# LTC6811_slave_12s_rev0.net
KiCad netlist of a schematic drawn in EAGLE
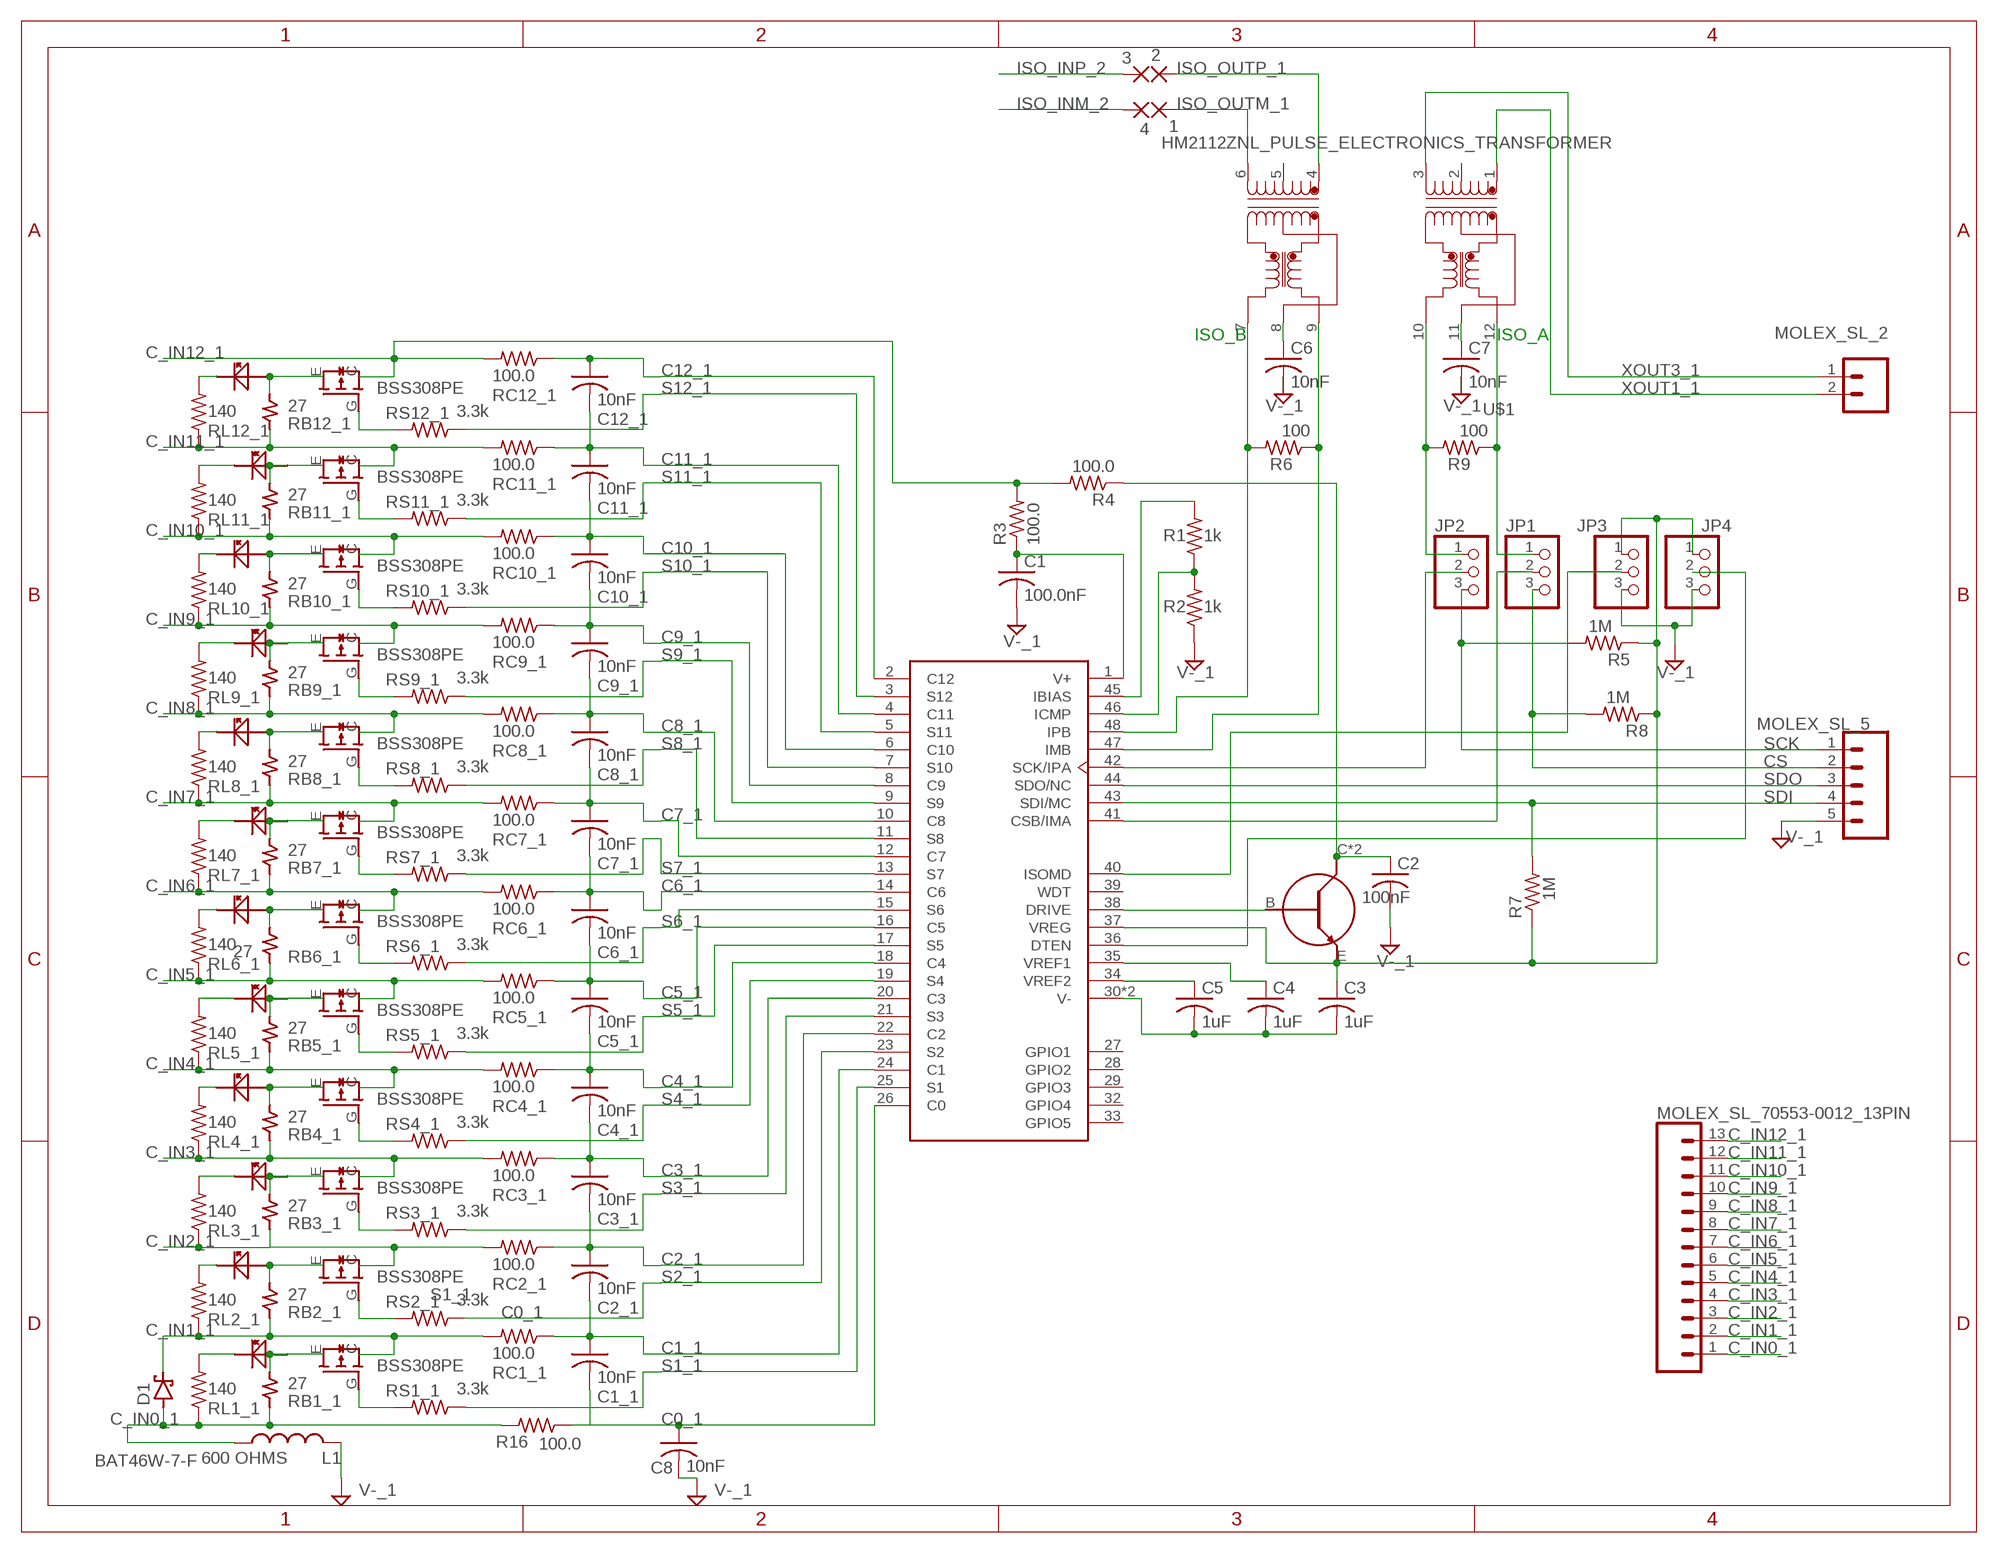
[diagram p0: schematic, sheet 1]

(export (version "E")
  (design (tool "Eeschema 10.0.6"))
  (components
    (comp (ref "1")
      (value "WIREPAD2,15/1,0")
      (footprint "eagle-import:2,15_1,0")
      (libsource (lib "eagle-import") (part "WIREPAD2,15/1,0"))
    )
    (comp (ref "2")
      (value "WIREPAD2,15/1,0")
      (footprint "eagle-import:2,15_1,0")
      (libsource (lib "eagle-import") (part "WIREPAD2,15/1,0"))
    )
    (comp (ref "3")
      (value "WIREPAD2,15/1,0")
      (footprint "eagle-import:2,15_1,0")
      (libsource (lib "eagle-import") (part "WIREPAD2,15/1,0"))
    )
    (comp (ref "4")
      (value "WIREPAD2,15/1,0")
      (footprint "eagle-import:2,15_1,0")
      (libsource (lib "eagle-import") (part "WIREPAD2,15/1,0"))
    )
    (comp (ref "C1")
      (value "100.0nF")
      (footprint "eagle-import:C0805")
      (libsource (lib "eagle-import") (part "C-USC0805"))
    )
    (comp (ref "C1_1")
      (value "10nF")
      (footprint "eagle-import:C0805")
      (libsource (lib "eagle-import") (part "C-USC0805"))
    )
    (comp (ref "C2")
      (value "100nF")
      (footprint "eagle-import:C0805")
      (libsource (lib "eagle-import") (part "C-USC0805"))
    )
    (comp (ref "C2_1")
      (value "10nF")
      (footprint "eagle-import:C0805")
      (libsource (lib "eagle-import") (part "C-USC0805"))
    )
    (comp (ref "C3")
      (value "1uF")
      (footprint "eagle-import:C0805")
      (libsource (lib "eagle-import") (part "C-USC0805"))
    )
    (comp (ref "C3_1")
      (value "10nF")
      (footprint "eagle-import:C0805")
      (libsource (lib "eagle-import") (part "C-USC0805"))
    )
    (comp (ref "C4")
      (value "1uF")
      (footprint "eagle-import:C0805")
      (libsource (lib "eagle-import") (part "C-USC0805"))
    )
    (comp (ref "C4_1")
      (value "10nF")
      (footprint "eagle-import:C0805")
      (libsource (lib "eagle-import") (part "C-USC0805"))
    )
    (comp (ref "C5")
      (value "1uF")
      (footprint "eagle-import:C0805")
      (libsource (lib "eagle-import") (part "C-USC0805"))
    )
    (comp (ref "C5_1")
      (value "10nF")
      (footprint "eagle-import:C0805")
      (libsource (lib "eagle-import") (part "C-USC0805"))
    )
    (comp (ref "C6")
      (value "10nF")
      (footprint "eagle-import:C0805")
      (libsource (lib "eagle-import") (part "C-USC0805"))
    )
    (comp (ref "C6_1")
      (value "10nF")
      (footprint "eagle-import:C0805")
      (libsource (lib "eagle-import") (part "C-USC0805"))
    )
    (comp (ref "C7")
      (value "10nF")
      (footprint "eagle-import:C0805")
      (libsource (lib "eagle-import") (part "C-USC0805"))
    )
    (comp (ref "C7_1")
      (value "10nF")
      (footprint "eagle-import:C0805")
      (libsource (lib "eagle-import") (part "C-USC0805"))
    )
    (comp (ref "C8")
      (value "10nF")
      (footprint "eagle-import:C0805")
      (libsource (lib "eagle-import") (part "C-USC0805"))
    )
    (comp (ref "C8_1")
      (value "10nF")
      (footprint "eagle-import:C0805")
      (libsource (lib "eagle-import") (part "C-USC0805"))
    )
    (comp (ref "C9_1")
      (value "10nF")
      (footprint "eagle-import:C0805")
      (libsource (lib "eagle-import") (part "C-USC0805"))
    )
    (comp (ref "C10_1")
      (value "10nF")
      (footprint "eagle-import:C0805")
      (libsource (lib "eagle-import") (part "C-USC0805"))
    )
    (comp (ref "C11_1")
      (value "10nF")
      (footprint "eagle-import:C0805")
      (libsource (lib "eagle-import") (part "C-USC0805"))
    )
    (comp (ref "C12_1")
      (value "10nF")
      (footprint "eagle-import:C0805")
      (libsource (lib "eagle-import") (part "C-USC0805"))
    )
    (comp (ref "D1")
      (value "BAT46W-7-F")
      (footprint "eagle-import:SOD123")
      (libsource (lib "eagle-import") (part "BAT46W-7-F"))
    )
    (comp (ref "DZT5551-13")
      (value "DZT5551-13")
      (footprint "eagle-import:SOT223-4")
      (libsource (lib "eagle-import") (part "DZT5551-13"))
    )
    (comp (ref "JP1")
      (value "PINHD-1X3")
      (footprint "eagle-import:1X03")
      (libsource (lib "eagle-import") (part "PINHD-1X3"))
    )
    (comp (ref "JP2")
      (value "PINHD-1X3")
      (footprint "eagle-import:1X03")
      (libsource (lib "eagle-import") (part "PINHD-1X3"))
    )
    (comp (ref "JP3")
      (value "PINHD-1X3")
      (footprint "eagle-import:1X03")
      (libsource (lib "eagle-import") (part "PINHD-1X3"))
    )
    (comp (ref "JP4")
      (value "PINHD-1X3")
      (footprint "eagle-import:1X03")
      (libsource (lib "eagle-import") (part "PINHD-1X3"))
    )
    (comp (ref "L1")
      (value "600 OHMS")
      (footprint "eagle-import:0805_COMPONENT")
      (libsource (lib "eagle-import") (part "0805_FERRITEBEAD_INDUCTOR"))
    )
    (comp (ref "LED1_3")
      (value "LED_0805")
      (footprint "eagle-import:0805_COMPONENT")
      (libsource (lib "eagle-import") (part "LED_0805"))
    )
    (comp (ref "LED1_4")
      (value "LED_0805")
      (footprint "eagle-import:0805_COMPONENT")
      (libsource (lib "eagle-import") (part "LED_0805"))
    )
    (comp (ref "LED1_5")
      (value "LED_0805")
      (footprint "eagle-import:0805_COMPONENT")
      (libsource (lib "eagle-import") (part "LED_0805"))
    )
    (comp (ref "LED1_6")
      (value "LED_0805")
      (footprint "eagle-import:0805_COMPONENT")
      (libsource (lib "eagle-import") (part "LED_0805"))
    )
    (comp (ref "LED1_7")
      (value "LED_0805")
      (footprint "eagle-import:0805_COMPONENT")
      (libsource (lib "eagle-import") (part "LED_0805"))
    )
    (comp (ref "LED1_8")
      (value "LED_0805")
      (footprint "eagle-import:0805_COMPONENT")
      (libsource (lib "eagle-import") (part "LED_0805"))
    )
    (comp (ref "LED1_9")
      (value "LED_0805")
      (footprint "eagle-import:0805_COMPONENT")
      (libsource (lib "eagle-import") (part "LED_0805"))
    )
    (comp (ref "LED1_10")
      (value "LED_0805")
      (footprint "eagle-import:0805_COMPONENT")
      (libsource (lib "eagle-import") (part "LED_0805"))
    )
    (comp (ref "LED1_11")
      (value "LED_0805")
      (footprint "eagle-import:0805_COMPONENT")
      (libsource (lib "eagle-import") (part "LED_0805"))
    )
    (comp (ref "LED1_12")
      (value "LED_0805")
      (footprint "eagle-import:0805_COMPONENT")
      (libsource (lib "eagle-import") (part "LED_0805"))
    )
    (comp (ref "LED1_13")
      (value "LED_0805")
      (footprint "eagle-import:0805_COMPONENT")
      (libsource (lib "eagle-import") (part "LED_0805"))
    )
    (comp (ref "LED1_14")
      (value "LED_0805")
      (footprint "eagle-import:0805_COMPONENT")
      (libsource (lib "eagle-import") (part "LED_0805"))
    )
    (comp (ref "MOLEX_SL_2")
      (value "CONN_02")
      (footprint "eagle-import:1X02")
      (libsource (lib "eagle-import") (part "CONN_02"))
    )
    (comp (ref "MOLEX_SL_5")
      (value "CONN_05")
      (footprint "eagle-import:1X05")
      (libsource (lib "eagle-import") (part "CONN_05"))
    )
    (comp (ref "MOLEX_SL_70553-0012_13PIN")
      (value "CONN_13")
      (footprint "eagle-import:1X13")
      (libsource (lib "eagle-import") (part "CONN_13"))
    )
    (comp (ref "R1")
      (value "1k")
      (footprint "eagle-import:R0805")
      (libsource (lib "eagle-import") (part "R-US_R0805"))
    )
    (comp (ref "R2")
      (value "1k")
      (footprint "eagle-import:R0805")
      (libsource (lib "eagle-import") (part "R-US_R0805"))
    )
    (comp (ref "R3")
      (value "100.0")
      (footprint "eagle-import:R0805")
      (libsource (lib "eagle-import") (part "R-US_R0805"))
    )
    (comp (ref "R4")
      (value "100.0")
      (footprint "eagle-import:R0805")
      (libsource (lib "eagle-import") (part "R-US_R0805"))
    )
    (comp (ref "R5")
      (value "1M")
      (footprint "eagle-import:R0805")
      (libsource (lib "eagle-import") (part "R-US_R0805"))
    )
    (comp (ref "R6")
      (value "100")
      (footprint "eagle-import:R0805")
      (libsource (lib "eagle-import") (part "R-US_R0805"))
    )
    (comp (ref "R7")
      (value "1M")
      (footprint "eagle-import:R0805")
      (libsource (lib "eagle-import") (part "R-US_R0805"))
    )
    (comp (ref "R8")
      (value "1M")
      (footprint "eagle-import:R0805")
      (libsource (lib "eagle-import") (part "R-US_R0805"))
    )
    (comp (ref "R9")
      (value "100")
      (footprint "eagle-import:R0805")
      (libsource (lib "eagle-import") (part "R-US_R0805"))
    )
    (comp (ref "R16")
      (value "100.0")
      (footprint "eagle-import:R0805")
      (libsource (lib "eagle-import") (part "R-US_R0805"))
    )
    (comp (ref "RB1_1")
      (value "27")
      (footprint "eagle-import:2817_COMPONENT")
      (libsource (lib "eagle-import") (part "2817_RESISTOR"))
    )
    (comp (ref "RB2_1")
      (value "27")
      (footprint "eagle-import:2817_COMPONENT")
      (libsource (lib "eagle-import") (part "2817_RESISTOR"))
    )
    (comp (ref "RB3_1")
      (value "27")
      (footprint "eagle-import:2817_COMPONENT")
      (libsource (lib "eagle-import") (part "2817_RESISTOR"))
    )
    (comp (ref "RB4_1")
      (value "27")
      (footprint "eagle-import:2817_COMPONENT")
      (libsource (lib "eagle-import") (part "2817_RESISTOR"))
    )
    (comp (ref "RB5_1")
      (value "27")
      (footprint "eagle-import:2817_COMPONENT")
      (libsource (lib "eagle-import") (part "2817_RESISTOR"))
    )
    (comp (ref "RB6_1")
      (value "27")
      (footprint "eagle-import:2817_COMPONENT")
      (libsource (lib "eagle-import") (part "2817_RESISTOR"))
    )
    (comp (ref "RB7_1")
      (value "27")
      (footprint "eagle-import:2817_COMPONENT")
      (libsource (lib "eagle-import") (part "2817_RESISTOR"))
    )
    (comp (ref "RB8_1")
      (value "27")
      (footprint "eagle-import:2817_COMPONENT")
      (libsource (lib "eagle-import") (part "2817_RESISTOR"))
    )
    (comp (ref "RB9_1")
      (value "27")
      (footprint "eagle-import:2817_COMPONENT")
      (libsource (lib "eagle-import") (part "2817_RESISTOR"))
    )
    (comp (ref "RB10_1")
      (value "27")
      (footprint "eagle-import:2817_COMPONENT")
      (libsource (lib "eagle-import") (part "2817_RESISTOR"))
    )
    (comp (ref "RB11_1")
      (value "27")
      (footprint "eagle-import:2817_COMPONENT")
      (libsource (lib "eagle-import") (part "2817_RESISTOR"))
    )
    (comp (ref "RB12_1")
      (value "27")
      (footprint "eagle-import:2817_COMPONENT")
      (libsource (lib "eagle-import") (part "2817_RESISTOR"))
    )
    (comp (ref "RC1_1")
      (value "100.0")
      (footprint "eagle-import:R0805")
      (libsource (lib "eagle-import") (part "R-US_R0805"))
    )
    (comp (ref "RC2_1")
      (value "100.0")
      (footprint "eagle-import:R0805")
      (libsource (lib "eagle-import") (part "R-US_R0805"))
    )
    (comp (ref "RC3_1")
      (value "100.0")
      (footprint "eagle-import:R0805")
      (libsource (lib "eagle-import") (part "R-US_R0805"))
    )
    (comp (ref "RC4_1")
      (value "100.0")
      (footprint "eagle-import:R0805")
      (libsource (lib "eagle-import") (part "R-US_R0805"))
    )
    (comp (ref "RC5_1")
      (value "100.0")
      (footprint "eagle-import:R0805")
      (libsource (lib "eagle-import") (part "R-US_R0805"))
    )
    (comp (ref "RC6_1")
      (value "100.0")
      (footprint "eagle-import:R0805")
      (libsource (lib "eagle-import") (part "R-US_R0805"))
    )
    (comp (ref "RC7_1")
      (value "100.0")
      (footprint "eagle-import:R0805")
      (libsource (lib "eagle-import") (part "R-US_R0805"))
    )
    (comp (ref "RC8_1")
      (value "100.0")
      (footprint "eagle-import:R0805")
      (libsource (lib "eagle-import") (part "R-US_R0805"))
    )
    (comp (ref "RC9_1")
      (value "100.0")
      (footprint "eagle-import:R0805")
      (libsource (lib "eagle-import") (part "R-US_R0805"))
    )
    (comp (ref "RC10_1")
      (value "100.0")
      (footprint "eagle-import:R0805")
      (libsource (lib "eagle-import") (part "R-US_R0805"))
    )
    (comp (ref "RC11_1")
      (value "100.0")
      (footprint "eagle-import:R0805")
      (libsource (lib "eagle-import") (part "R-US_R0805"))
    )
    (comp (ref "RC12_1")
      (value "100.0")
      (footprint "eagle-import:R0805")
      (libsource (lib "eagle-import") (part "R-US_R0805"))
    )
    (comp (ref "RL1_1")
      (value "140")
      (footprint "eagle-import:R0805")
      (libsource (lib "eagle-import") (part "R-US_R0805"))
    )
    (comp (ref "RL2_1")
      (value "140")
      (footprint "eagle-import:R0805")
      (libsource (lib "eagle-import") (part "R-US_R0805"))
    )
    (comp (ref "RL3_1")
      (value "140")
      (footprint "eagle-import:R0805")
      (libsource (lib "eagle-import") (part "R-US_R0805"))
    )
    (comp (ref "RL4_1")
      (value "140")
      (footprint "eagle-import:R0805")
      (libsource (lib "eagle-import") (part "R-US_R0805"))
    )
    (comp (ref "RL5_1")
      (value "140")
      (footprint "eagle-import:R0805")
      (libsource (lib "eagle-import") (part "R-US_R0805"))
    )
    (comp (ref "RL6_1")
      (value "140")
      (footprint "eagle-import:R0805")
      (libsource (lib "eagle-import") (part "R-US_R0805"))
    )
    (comp (ref "RL7_1")
      (value "140")
      (footprint "eagle-import:R0805")
      (libsource (lib "eagle-import") (part "R-US_R0805"))
    )
    (comp (ref "RL8_1")
      (value "140")
      (footprint "eagle-import:R0805")
      (libsource (lib "eagle-import") (part "R-US_R0805"))
    )
    (comp (ref "RL9_1")
      (value "140")
      (footprint "eagle-import:R0805")
      (libsource (lib "eagle-import") (part "R-US_R0805"))
    )
    (comp (ref "RL10_1")
      (value "140")
      (footprint "eagle-import:R0805")
      (libsource (lib "eagle-import") (part "R-US_R0805"))
    )
    (comp (ref "RL11_1")
      (value "140")
      (footprint "eagle-import:R0805")
      (libsource (lib "eagle-import") (part "R-US_R0805"))
    )
    (comp (ref "RL12_1")
      (value "140")
      (footprint "eagle-import:R0805")
      (libsource (lib "eagle-import") (part "R-US_R0805"))
    )
    (comp (ref "RS1_1")
      (value "3.3k")
      (footprint "eagle-import:R0805")
      (libsource (lib "eagle-import") (part "R-US_R0805"))
    )
    (comp (ref "RS2_1")
      (value "3.3k")
      (footprint "eagle-import:R0805")
      (libsource (lib "eagle-import") (part "R-US_R0805"))
    )
    (comp (ref "RS3_1")
      (value "3.3k")
      (footprint "eagle-import:R0805")
      (libsource (lib "eagle-import") (part "R-US_R0805"))
    )
    (comp (ref "RS4_1")
      (value "3.3k")
      (footprint "eagle-import:R0805")
      (libsource (lib "eagle-import") (part "R-US_R0805"))
    )
    (comp (ref "RS5_1")
      (value "3.3k")
      (footprint "eagle-import:R0805")
      (libsource (lib "eagle-import") (part "R-US_R0805"))
    )
    (comp (ref "RS6_1")
      (value "3.3k")
      (footprint "eagle-import:R0805")
      (libsource (lib "eagle-import") (part "R-US_R0805"))
    )
    (comp (ref "RS7_1")
      (value "3.3k")
      (footprint "eagle-import:R0805")
      (libsource (lib "eagle-import") (part "R-US_R0805"))
    )
    (comp (ref "RS8_1")
      (value "3.3k")
      (footprint "eagle-import:R0805")
      (libsource (lib "eagle-import") (part "R-US_R0805"))
    )
    (comp (ref "RS9_1")
      (value "3.3k")
      (footprint "eagle-import:R0805")
      (libsource (lib "eagle-import") (part "R-US_R0805"))
    )
    (comp (ref "RS10_1")
      (value "3.3k")
      (footprint "eagle-import:R0805")
      (libsource (lib "eagle-import") (part "R-US_R0805"))
    )
    (comp (ref "RS11_1")
      (value "3.3k")
      (footprint "eagle-import:R0805")
      (libsource (lib "eagle-import") (part "R-US_R0805"))
    )
    (comp (ref "RS12_1")
      (value "3.3k")
      (footprint "eagle-import:R0805")
      (libsource (lib "eagle-import") (part "R-US_R0805"))
    )
    (comp (ref "T1_3")
      (value "BSS308PEH6327")
      (footprint "eagle-import:SOT23")
      (libsource (lib "eagle-import") (part "BSS308PEH6327"))
    )
    (comp (ref "T1_4")
      (value "BSS308PEH6327")
      (footprint "eagle-import:SOT23")
      (libsource (lib "eagle-import") (part "BSS308PEH6327"))
    )
    (comp (ref "T1_5")
      (value "BSS308PEH6327")
      (footprint "eagle-import:SOT23")
      (libsource (lib "eagle-import") (part "BSS308PEH6327"))
    )
    (comp (ref "T1_6")
      (value "BSS308PEH6327")
      (footprint "eagle-import:SOT23")
      (libsource (lib "eagle-import") (part "BSS308PEH6327"))
    )
    (comp (ref "T1_7")
      (value "BSS308PEH6327")
      (footprint "eagle-import:SOT23")
      (libsource (lib "eagle-import") (part "BSS308PEH6327"))
    )
    (comp (ref "T1_8")
      (value "BSS308PEH6327")
      (footprint "eagle-import:SOT23")
      (libsource (lib "eagle-import") (part "BSS308PEH6327"))
    )
    (comp (ref "T1_9")
      (value "BSS308PEH6327")
      (footprint "eagle-import:SOT23")
      (libsource (lib "eagle-import") (part "BSS308PEH6327"))
    )
    (comp (ref "T1_10")
      (value "BSS308PEH6327")
      (footprint "eagle-import:SOT23")
      (libsource (lib "eagle-import") (part "BSS308PEH6327"))
    )
    (comp (ref "T1_11")
      (value "BSS308PEH6327")
      (footprint "eagle-import:SOT23")
      (libsource (lib "eagle-import") (part "BSS308PEH6327"))
    )
    (comp (ref "T1_12")
      (value "BSS308PEH6327")
      (footprint "eagle-import:SOT23")
      (libsource (lib "eagle-import") (part "BSS308PEH6327"))
    )
    (comp (ref "T1_13")
      (value "BSS308PEH6327")
      (footprint "eagle-import:SOT23")
      (libsource (lib "eagle-import") (part "BSS308PEH6327"))
    )
    (comp (ref "T1_14")
      (value "BSS308PEH6327")
      (footprint "eagle-import:SOT23")
      (libsource (lib "eagle-import") (part "BSS308PEH6327"))
    )
    (comp (ref "U$1")
      (value "HM2112ZNL_PULSE_ELECTRONICS_TRANSFORMER")
      (footprint "eagle-import:HM2112ZNL_12SMT")
      (libsource (lib "eagle-import") (part "HM2112ZNL_PULSE_ELECTRONICS_TRANSFORMER"))
    )
    (comp (ref "U1")
      (value "LTC6811HG-2#PBF")
      (footprint "eagle-import:LTC6811-1")
      (fields (field (name "MF") "Linear Technology/Analog"))
      (libsource (lib "eagle-import") (part "LTC6811HG-2#PBF"))
    )
  )
  (nets
    (net (code "1") (name "C0_1") (class "Default")
      (node (ref "C8") (pin "1") (pinfunction "1_1") (pintype "passive"))
      (node (ref "R16") (pin "1") (pinfunction "1_1") (pintype "passive"))
      (node (ref "U1") (pin "26") (pinfunction "C0_26") (pintype "input"))
    )
    (net (code "2") (name "C1_1") (class "Default")
      (node (ref "C1_1") (pin "1") (pinfunction "1_1") (pintype "passive"))
      (node (ref "C2_1") (pin "2") (pinfunction "2_2") (pintype "passive"))
      (node (ref "RC1_1") (pin "1") (pinfunction "1_1") (pintype "passive"))
      (node (ref "U1") (pin "24") (pinfunction "C1_24") (pintype "input"))
    )
    (net (code "3") (name "C2_1") (class "Default")
      (node (ref "C2_1") (pin "1") (pinfunction "1_1") (pintype "passive"))
      (node (ref "C3_1") (pin "2") (pinfunction "2_2") (pintype "passive"))
      (node (ref "RC2_1") (pin "1") (pinfunction "1_1") (pintype "passive"))
      (node (ref "U1") (pin "22") (pinfunction "C2_22") (pintype "input"))
    )
    (net (code "4") (name "C3_1") (class "Default")
      (node (ref "C3_1") (pin "1") (pinfunction "1_1") (pintype "passive"))
      (node (ref "C4_1") (pin "2") (pinfunction "2_2") (pintype "passive"))
      (node (ref "RC3_1") (pin "1") (pinfunction "1_1") (pintype "passive"))
      (node (ref "U1") (pin "20") (pinfunction "C3_20") (pintype "input"))
    )
    (net (code "5") (name "C4_1") (class "Default")
      (node (ref "C4_1") (pin "1") (pinfunction "1_1") (pintype "passive"))
      (node (ref "C5_1") (pin "2") (pinfunction "2_2") (pintype "passive"))
      (node (ref "RC4_1") (pin "1") (pinfunction "1_1") (pintype "passive"))
      (node (ref "U1") (pin "18") (pinfunction "C4_18") (pintype "input"))
    )
    (net (code "6") (name "C5_1") (class "Default")
      (node (ref "C5_1") (pin "1") (pinfunction "1_1") (pintype "passive"))
      (node (ref "C6_1") (pin "2") (pinfunction "2_2") (pintype "passive"))
      (node (ref "RC5_1") (pin "1") (pinfunction "1_1") (pintype "passive"))
      (node (ref "U1") (pin "16") (pinfunction "C5_16") (pintype "input"))
    )
    (net (code "7") (name "C6_1") (class "Default")
      (node (ref "C6_1") (pin "1") (pinfunction "1_1") (pintype "passive"))
      (node (ref "C7_1") (pin "2") (pinfunction "2_2") (pintype "passive"))
      (node (ref "RC6_1") (pin "1") (pinfunction "1_1") (pintype "passive"))
      (node (ref "U1") (pin "14") (pinfunction "C6_14") (pintype "input"))
    )
    (net (code "8") (name "C7_1") (class "Default")
      (node (ref "C7_1") (pin "1") (pinfunction "1_1") (pintype "passive"))
      (node (ref "C8_1") (pin "2") (pinfunction "2_2") (pintype "passive"))
      (node (ref "RC7_1") (pin "1") (pinfunction "1_1") (pintype "passive"))
      (node (ref "U1") (pin "12") (pinfunction "C7_12") (pintype "input"))
    )
    (net (code "9") (name "C8_1") (class "Default")
      (node (ref "C8_1") (pin "1") (pinfunction "1_1") (pintype "passive"))
      (node (ref "C9_1") (pin "2") (pinfunction "2_2") (pintype "passive"))
      (node (ref "RC8_1") (pin "1") (pinfunction "1_1") (pintype "passive"))
      (node (ref "U1") (pin "10") (pinfunction "C8_10") (pintype "input"))
    )
    (net (code "10") (name "C9_1") (class "Default")
      (node (ref "C10_1") (pin "2") (pinfunction "2_2") (pintype "passive"))
      (node (ref "C9_1") (pin "1") (pinfunction "1_1") (pintype "passive"))
      (node (ref "RC9_1") (pin "1") (pinfunction "1_1") (pintype "passive"))
      (node (ref "U1") (pin "8") (pinfunction "C9_8") (pintype "input"))
    )
    (net (code "11") (name "C10_1") (class "Default")
      (node (ref "C10_1") (pin "1") (pinfunction "1_1") (pintype "passive"))
      (node (ref "C11_1") (pin "2") (pinfunction "2_2") (pintype "passive"))
      (node (ref "RC10_1") (pin "1") (pinfunction "1_1") (pintype "passive"))
      (node (ref "U1") (pin "6") (pinfunction "C10_6") (pintype "input"))
    )
    (net (code "12") (name "C11_1") (class "Default")
      (node (ref "C11_1") (pin "1") (pinfunction "1_1") (pintype "passive"))
      (node (ref "C12_1") (pin "2") (pinfunction "2_2") (pintype "passive"))
      (node (ref "RC11_1") (pin "1") (pinfunction "1_1") (pintype "passive"))
      (node (ref "U1") (pin "4") (pinfunction "C11_4") (pintype "input"))
    )
    (net (code "13") (name "C12_1") (class "Default")
      (node (ref "C12_1") (pin "1") (pinfunction "1_1") (pintype "passive"))
      (node (ref "RC12_1") (pin "1") (pinfunction "1_1") (pintype "passive"))
      (node (ref "U1") (pin "2") (pinfunction "C12_2") (pintype "input"))
    )
    (net (code "14") (name "CS") (class "Default")
      (node (ref "JP1") (pin "3") (pinfunction "3_3") (pintype "passive"))
      (node (ref "MOLEX_SL_5") (pin "2") (pinfunction "2_2") (pintype "passive"))
      (node (ref "R8") (pin "2") (pinfunction "2_2") (pintype "passive"))
    )
    (net (code "15") (name "C_IN0_1") (class "Default")
      (node (ref "D1") (pin "A") (pinfunction "A_A") (pintype "passive"))
      (node (ref "L1") (pin "1") (pinfunction "1_1") (pintype "passive"))
      (node (ref "MOLEX_SL_70553-0012_13PIN") (pin "1") (pinfunction "1_1") (pintype "passive"))
      (node (ref "R16") (pin "2") (pinfunction "2_2") (pintype "passive"))
      (node (ref "RB1_1") (pin "2") (pinfunction "P$2_2") (pintype "bidirectional"))
      (node (ref "RL1_1") (pin "1") (pinfunction "1_1") (pintype "passive"))
    )
    (net (code "16") (name "C_IN1_1") (class "Default")
      (node (ref "D1") (pin "C") (pinfunction "C_C") (pintype "passive"))
      (node (ref "MOLEX_SL_70553-0012_13PIN") (pin "2") (pinfunction "2_2") (pintype "passive"))
      (node (ref "RB2_1") (pin "2") (pinfunction "P$2_2") (pintype "bidirectional"))
      (node (ref "RC1_1") (pin "2") (pinfunction "2_2") (pintype "passive"))
      (node (ref "RL2_1") (pin "1") (pinfunction "1_1") (pintype "passive"))
      (node (ref "T1_3") (pin "C") (pinfunction "C_C") (pintype "bidirectional"))
    )
    (net (code "17") (name "C_IN2_1") (class "Default")
      (node (ref "MOLEX_SL_70553-0012_13PIN") (pin "3") (pinfunction "3_3") (pintype "passive"))
      (node (ref "RB3_1") (pin "2") (pinfunction "P$2_2") (pintype "bidirectional"))
      (node (ref "RC2_1") (pin "2") (pinfunction "2_2") (pintype "passive"))
      (node (ref "RL3_1") (pin "1") (pinfunction "1_1") (pintype "passive"))
      (node (ref "T1_4") (pin "C") (pinfunction "C_C") (pintype "bidirectional"))
    )
    (net (code "18") (name "C_IN3_1") (class "Default")
      (node (ref "MOLEX_SL_70553-0012_13PIN") (pin "4") (pinfunction "4_4") (pintype "passive"))
      (node (ref "RB4_1") (pin "2") (pinfunction "P$2_2") (pintype "bidirectional"))
      (node (ref "RC3_1") (pin "2") (pinfunction "2_2") (pintype "passive"))
      (node (ref "RL4_1") (pin "1") (pinfunction "1_1") (pintype "passive"))
      (node (ref "T1_7") (pin "C") (pinfunction "C_C") (pintype "bidirectional"))
    )
    (net (code "19") (name "C_IN4_1") (class "Default")
      (node (ref "MOLEX_SL_70553-0012_13PIN") (pin "5") (pinfunction "5_5") (pintype "passive"))
      (node (ref "RB5_1") (pin "2") (pinfunction "P$2_2") (pintype "bidirectional"))
      (node (ref "RC4_1") (pin "2") (pinfunction "2_2") (pintype "passive"))
      (node (ref "RL5_1") (pin "1") (pinfunction "1_1") (pintype "passive"))
      (node (ref "T1_8") (pin "C") (pinfunction "C_C") (pintype "bidirectional"))
    )
    (net (code "20") (name "C_IN5_1") (class "Default")
      (node (ref "MOLEX_SL_70553-0012_13PIN") (pin "6") (pinfunction "6_6") (pintype "passive"))
      (node (ref "RB6_1") (pin "2") (pinfunction "P$2_2") (pintype "bidirectional"))
      (node (ref "RC5_1") (pin "2") (pinfunction "2_2") (pintype "passive"))
      (node (ref "RL6_1") (pin "1") (pinfunction "1_1") (pintype "passive"))
      (node (ref "T1_5") (pin "C") (pinfunction "C_C") (pintype "bidirectional"))
    )
    (net (code "21") (name "C_IN6_1") (class "Default")
      (node (ref "MOLEX_SL_70553-0012_13PIN") (pin "7") (pinfunction "7_7") (pintype "passive"))
      (node (ref "RB7_1") (pin "2") (pinfunction "P$2_2") (pintype "bidirectional"))
      (node (ref "RC6_1") (pin "2") (pinfunction "2_2") (pintype "passive"))
      (node (ref "RL7_1") (pin "1") (pinfunction "1_1") (pintype "passive"))
      (node (ref "T1_6") (pin "C") (pinfunction "C_C") (pintype "bidirectional"))
    )
    (net (code "22") (name "C_IN7_1") (class "Default")
      (node (ref "MOLEX_SL_70553-0012_13PIN") (pin "8") (pinfunction "8_8") (pintype "passive"))
      (node (ref "RB8_1") (pin "2") (pinfunction "P$2_2") (pintype "bidirectional"))
      (node (ref "RC7_1") (pin "2") (pinfunction "2_2") (pintype "passive"))
      (node (ref "RL8_1") (pin "1") (pinfunction "1_1") (pintype "passive"))
      (node (ref "T1_9") (pin "C") (pinfunction "C_C") (pintype "bidirectional"))
    )
    (net (code "23") (name "C_IN8_1") (class "Default")
      (node (ref "MOLEX_SL_70553-0012_13PIN") (pin "9") (pinfunction "9_9") (pintype "passive"))
      (node (ref "RB9_1") (pin "2") (pinfunction "P$2_2") (pintype "bidirectional"))
      (node (ref "RC8_1") (pin "2") (pinfunction "2_2") (pintype "passive"))
      (node (ref "RL9_1") (pin "1") (pinfunction "1_1") (pintype "passive"))
      (node (ref "T1_10") (pin "C") (pinfunction "C_C") (pintype "bidirectional"))
    )
    (net (code "24") (name "C_IN9_1") (class "Default")
      (node (ref "MOLEX_SL_70553-0012_13PIN") (pin "10") (pinfunction "10_10") (pintype "passive"))
      (node (ref "RB10_1") (pin "2") (pinfunction "P$2_2") (pintype "bidirectional"))
      (node (ref "RC9_1") (pin "2") (pinfunction "2_2") (pintype "passive"))
      (node (ref "RL10_1") (pin "1") (pinfunction "1_1") (pintype "passive"))
      (node (ref "T1_11") (pin "C") (pinfunction "C_C") (pintype "bidirectional"))
    )
    (net (code "25") (name "C_IN10_1") (class "Default")
      (node (ref "MOLEX_SL_70553-0012_13PIN") (pin "11") (pinfunction "11_11") (pintype "passive"))
      (node (ref "RB11_1") (pin "2") (pinfunction "P$2_2") (pintype "bidirectional"))
      (node (ref "RC10_1") (pin "2") (pinfunction "2_2") (pintype "passive"))
      (node (ref "RL11_1") (pin "1") (pinfunction "1_1") (pintype "passive"))
      (node (ref "T1_12") (pin "C") (pinfunction "C_C") (pintype "bidirectional"))
    )
    (net (code "26") (name "C_IN11_1") (class "Default")
      (node (ref "MOLEX_SL_70553-0012_13PIN") (pin "12") (pinfunction "12_12") (pintype "passive"))
      (node (ref "RB12_1") (pin "2") (pinfunction "P$2_2") (pintype "bidirectional"))
      (node (ref "RC11_1") (pin "2") (pinfunction "2_2") (pintype "passive"))
      (node (ref "RL12_1") (pin "1") (pinfunction "1_1") (pintype "passive"))
      (node (ref "T1_13") (pin "C") (pinfunction "C_C") (pintype "bidirectional"))
    )
    (net (code "27") (name "C_IN12_1") (class "Default")
      (node (ref "MOLEX_SL_70553-0012_13PIN") (pin "13") (pinfunction "13_13") (pintype "passive"))
      (node (ref "R3") (pin "2") (pinfunction "2_2") (pintype "passive"))
      (node (ref "R4") (pin "2") (pinfunction "2_2") (pintype "passive"))
      (node (ref "RC12_1") (pin "2") (pinfunction "2_2") (pintype "passive"))
      (node (ref "T1_14") (pin "C") (pinfunction "C_C") (pintype "bidirectional"))
    )
    (net (code "28") (name "ISO_INM_2") (class "Default")
      (node (ref "4") (pin "1") (pinfunction "P_1") (pintype "passive"))
    )
    (net (code "29") (name "ISO_INP_2") (class "Default")
      (node (ref "3") (pin "1") (pinfunction "P_1") (pintype "passive"))
    )
    (net (code "30") (name "ISO_OUTM_1") (class "Default")
      (node (ref "1") (pin "1") (pinfunction "P_1") (pintype "passive"))
      (node (ref "U$1") (pin "6") (pinfunction "6_6") (pintype "bidirectional"))
    )
    (net (code "31") (name "ISO_OUTP_1") (class "Default")
      (node (ref "2") (pin "1") (pinfunction "P_1") (pintype "passive"))
      (node (ref "U$1") (pin "4") (pinfunction "4_4") (pintype "bidirectional"))
    )
    (net (code "32") (name "Net-(C2-Pad1)") (class "Default")
      (node (ref "C2") (pin "1") (pinfunction "1_1") (pintype "passive"))
      (node (ref "DZT5551-13") (pin "C") (pinfunction "C_C") (pintype "bidirectional"))
      (node (ref "DZT5551-13") (pin "C@2") (pinfunction "C_C@2") (pintype "bidirectional"))
      (node (ref "R4") (pin "1") (pinfunction "1_1") (pintype "passive"))
    )
    (net (code "33") (name "Net-(C6-Pad1)") (class "Default")
      (node (ref "C6") (pin "1") (pinfunction "1_1") (pintype "passive"))
      (node (ref "U$1") (pin "8") (pinfunction "8_8") (pintype "bidirectional"))
    )
    (net (code "34") (name "Net-(C7-Pad1)") (class "Default")
      (node (ref "C7") (pin "1") (pinfunction "1_1") (pintype "passive"))
      (node (ref "U$1") (pin "11") (pinfunction "11_11") (pintype "bidirectional"))
    )
    (net (code "35") (name "Net-(JP1-Pad1)") (class "Default")
      (node (ref "JP1") (pin "1") (pinfunction "1_1") (pintype "passive"))
      (node (ref "R9") (pin "1") (pinfunction "1_1") (pintype "passive"))
      (node (ref "U$1") (pin "12") (pinfunction "12_12") (pintype "bidirectional"))
    )
    (net (code "36") (name "Net-(JP2-Pad1)") (class "Default")
      (node (ref "JP2") (pin "1") (pinfunction "1_1") (pintype "passive"))
      (node (ref "R9") (pin "2") (pinfunction "2_2") (pintype "passive"))
      (node (ref "U$1") (pin "10") (pinfunction "10_10") (pintype "bidirectional"))
    )
    (net (code "37") (name "Net-(LED1_3-P$1)") (class "Default")
      (node (ref "LED1_3") (pin "1") (pinfunction "P$1_1") (pintype "bidirectional"))
      (node (ref "RL1_1") (pin "2") (pinfunction "2_2") (pintype "passive"))
    )
    (net (code "38") (name "Net-(LED1_3-P$2)") (class "Default")
      (node (ref "LED1_3") (pin "2") (pinfunction "P$2_2") (pintype "bidirectional"))
      (node (ref "RB1_1") (pin "1") (pinfunction "P$1_1") (pintype "bidirectional"))
      (node (ref "T1_3") (pin "E") (pinfunction "E_E") (pintype "bidirectional"))
    )
    (net (code "39") (name "Net-(LED1_4-P$1)") (class "Default")
      (node (ref "LED1_4") (pin "1") (pinfunction "P$1_1") (pintype "bidirectional"))
      (node (ref "RL2_1") (pin "2") (pinfunction "2_2") (pintype "passive"))
    )
    (net (code "40") (name "Net-(LED1_4-P$2)") (class "Default")
      (node (ref "LED1_4") (pin "2") (pinfunction "P$2_2") (pintype "bidirectional"))
      (node (ref "RB2_1") (pin "1") (pinfunction "P$1_1") (pintype "bidirectional"))
      (node (ref "T1_4") (pin "E") (pinfunction "E_E") (pintype "bidirectional"))
    )
    (net (code "41") (name "Net-(LED1_5-P$1)") (class "Default")
      (node (ref "LED1_5") (pin "1") (pinfunction "P$1_1") (pintype "bidirectional"))
      (node (ref "RL5_1") (pin "2") (pinfunction "2_2") (pintype "passive"))
    )
    (net (code "42") (name "Net-(LED1_5-P$2)") (class "Default")
      (node (ref "LED1_5") (pin "2") (pinfunction "P$2_2") (pintype "bidirectional"))
      (node (ref "RB5_1") (pin "1") (pinfunction "P$1_1") (pintype "bidirectional"))
      (node (ref "T1_5") (pin "E") (pinfunction "E_E") (pintype "bidirectional"))
    )
    (net (code "43") (name "Net-(LED1_6-P$1)") (class "Default")
      (node (ref "LED1_6") (pin "1") (pinfunction "P$1_1") (pintype "bidirectional"))
      (node (ref "RL6_1") (pin "2") (pinfunction "2_2") (pintype "passive"))
    )
    (net (code "44") (name "Net-(LED1_6-P$2)") (class "Default")
      (node (ref "LED1_6") (pin "2") (pinfunction "P$2_2") (pintype "bidirectional"))
      (node (ref "RB6_1") (pin "1") (pinfunction "P$1_1") (pintype "bidirectional"))
      (node (ref "T1_6") (pin "E") (pinfunction "E_E") (pintype "bidirectional"))
    )
    (net (code "45") (name "Net-(LED1_7-P$1)") (class "Default")
      (node (ref "LED1_7") (pin "1") (pinfunction "P$1_1") (pintype "bidirectional"))
      (node (ref "RL3_1") (pin "2") (pinfunction "2_2") (pintype "passive"))
    )
    (net (code "46") (name "Net-(LED1_7-P$2)") (class "Default")
      (node (ref "LED1_7") (pin "2") (pinfunction "P$2_2") (pintype "bidirectional"))
      (node (ref "RB3_1") (pin "1") (pinfunction "P$1_1") (pintype "bidirectional"))
      (node (ref "T1_7") (pin "E") (pinfunction "E_E") (pintype "bidirectional"))
    )
    (net (code "47") (name "Net-(LED1_8-P$1)") (class "Default")
      (node (ref "LED1_8") (pin "1") (pinfunction "P$1_1") (pintype "bidirectional"))
      (node (ref "RL4_1") (pin "2") (pinfunction "2_2") (pintype "passive"))
    )
    (net (code "48") (name "Net-(LED1_8-P$2)") (class "Default")
      (node (ref "LED1_8") (pin "2") (pinfunction "P$2_2") (pintype "bidirectional"))
      (node (ref "RB4_1") (pin "1") (pinfunction "P$1_1") (pintype "bidirectional"))
      (node (ref "T1_8") (pin "E") (pinfunction "E_E") (pintype "bidirectional"))
    )
    (net (code "49") (name "Net-(LED1_9-P$1)") (class "Default")
      (node (ref "LED1_9") (pin "1") (pinfunction "P$1_1") (pintype "bidirectional"))
      (node (ref "RL7_1") (pin "2") (pinfunction "2_2") (pintype "passive"))
    )
    (net (code "50") (name "Net-(LED1_9-P$2)") (class "Default")
      (node (ref "LED1_9") (pin "2") (pinfunction "P$2_2") (pintype "bidirectional"))
      (node (ref "RB7_1") (pin "1") (pinfunction "P$1_1") (pintype "bidirectional"))
      (node (ref "T1_9") (pin "E") (pinfunction "E_E") (pintype "bidirectional"))
    )
    (net (code "51") (name "Net-(LED1_10-P$1)") (class "Default")
      (node (ref "LED1_10") (pin "1") (pinfunction "P$1_1") (pintype "bidirectional"))
      (node (ref "RL8_1") (pin "2") (pinfunction "2_2") (pintype "passive"))
    )
    (net (code "52") (name "Net-(LED1_10-P$2)") (class "Default")
      (node (ref "LED1_10") (pin "2") (pinfunction "P$2_2") (pintype "bidirectional"))
      (node (ref "RB8_1") (pin "1") (pinfunction "P$1_1") (pintype "bidirectional"))
      (node (ref "T1_10") (pin "E") (pinfunction "E_E") (pintype "bidirectional"))
    )
    (net (code "53") (name "Net-(LED1_11-P$1)") (class "Default")
      (node (ref "LED1_11") (pin "1") (pinfunction "P$1_1") (pintype "bidirectional"))
      (node (ref "RL9_1") (pin "2") (pinfunction "2_2") (pintype "passive"))
    )
    (net (code "54") (name "Net-(LED1_11-P$2)") (class "Default")
      (node (ref "LED1_11") (pin "2") (pinfunction "P$2_2") (pintype "bidirectional"))
      (node (ref "RB9_1") (pin "1") (pinfunction "P$1_1") (pintype "bidirectional"))
      (node (ref "T1_11") (pin "E") (pinfunction "E_E") (pintype "bidirectional"))
    )
    (net (code "55") (name "Net-(LED1_12-P$1)") (class "Default")
      (node (ref "LED1_12") (pin "1") (pinfunction "P$1_1") (pintype "bidirectional"))
      (node (ref "RL10_1") (pin "2") (pinfunction "2_2") (pintype "passive"))
    )
    (net (code "56") (name "Net-(LED1_12-P$2)") (class "Default")
      (node (ref "LED1_12") (pin "2") (pinfunction "P$2_2") (pintype "bidirectional"))
      (node (ref "RB10_1") (pin "1") (pinfunction "P$1_1") (pintype "bidirectional"))
      (node (ref "T1_12") (pin "E") (pinfunction "E_E") (pintype "bidirectional"))
    )
    (net (code "57") (name "Net-(LED1_13-P$1)") (class "Default")
      (node (ref "LED1_13") (pin "1") (pinfunction "P$1_1") (pintype "bidirectional"))
      (node (ref "RL11_1") (pin "2") (pinfunction "2_2") (pintype "passive"))
    )
    (net (code "58") (name "Net-(LED1_13-P$2)") (class "Default")
      (node (ref "LED1_13") (pin "2") (pinfunction "P$2_2") (pintype "bidirectional"))
      (node (ref "RB11_1") (pin "1") (pinfunction "P$1_1") (pintype "bidirectional"))
      (node (ref "T1_13") (pin "E") (pinfunction "E_E") (pintype "bidirectional"))
    )
    (net (code "59") (name "Net-(LED1_14-P$1)") (class "Default")
      (node (ref "LED1_14") (pin "1") (pinfunction "P$1_1") (pintype "bidirectional"))
      (node (ref "RL12_1") (pin "2") (pinfunction "2_2") (pintype "passive"))
    )
    (net (code "60") (name "Net-(LED1_14-P$2)") (class "Default")
      (node (ref "LED1_14") (pin "2") (pinfunction "P$2_2") (pintype "bidirectional"))
      (node (ref "RB12_1") (pin "1") (pinfunction "P$1_1") (pintype "bidirectional"))
      (node (ref "T1_14") (pin "E") (pinfunction "E_E") (pintype "bidirectional"))
    )
    (net (code "61") (name "Net-(T1_3-B)") (class "Default")
      (node (ref "RS1_1") (pin "2") (pinfunction "2_2") (pintype "passive"))
      (node (ref "T1_3") (pin "G") (pinfunction "B_G") (pintype "bidirectional"))
    )
    (net (code "62") (name "Net-(T1_4-B)") (class "Default")
      (node (ref "RS2_1") (pin "2") (pinfunction "2_2") (pintype "passive"))
      (node (ref "T1_4") (pin "G") (pinfunction "B_G") (pintype "bidirectional"))
    )
    (net (code "63") (name "Net-(T1_5-B)") (class "Default")
      (node (ref "RS5_1") (pin "2") (pinfunction "2_2") (pintype "passive"))
      (node (ref "T1_5") (pin "G") (pinfunction "B_G") (pintype "bidirectional"))
    )
    (net (code "64") (name "Net-(T1_6-B)") (class "Default")
      (node (ref "RS6_1") (pin "2") (pinfunction "2_2") (pintype "passive"))
      (node (ref "T1_6") (pin "G") (pinfunction "B_G") (pintype "bidirectional"))
    )
    (net (code "65") (name "Net-(T1_7-B)") (class "Default")
      (node (ref "RS3_1") (pin "2") (pinfunction "2_2") (pintype "passive"))
      (node (ref "T1_7") (pin "G") (pinfunction "B_G") (pintype "bidirectional"))
    )
    (net (code "66") (name "Net-(T1_8-B)") (class "Default")
      (node (ref "RS4_1") (pin "2") (pinfunction "2_2") (pintype "passive"))
      (node (ref "T1_8") (pin "G") (pinfunction "B_G") (pintype "bidirectional"))
    )
    (net (code "67") (name "Net-(T1_9-B)") (class "Default")
      (node (ref "RS7_1") (pin "2") (pinfunction "2_2") (pintype "passive"))
      (node (ref "T1_9") (pin "G") (pinfunction "B_G") (pintype "bidirectional"))
    )
    (net (code "68") (name "Net-(T1_10-B)") (class "Default")
      (node (ref "RS8_1") (pin "2") (pinfunction "2_2") (pintype "passive"))
      (node (ref "T1_10") (pin "G") (pinfunction "B_G") (pintype "bidirectional"))
    )
    (net (code "69") (name "Net-(T1_11-B)") (class "Default")
      (node (ref "RS9_1") (pin "2") (pinfunction "2_2") (pintype "passive"))
      (node (ref "T1_11") (pin "G") (pinfunction "B_G") (pintype "bidirectional"))
    )
    (net (code "70") (name "Net-(T1_12-B)") (class "Default")
      (node (ref "RS10_1") (pin "2") (pinfunction "2_2") (pintype "passive"))
      (node (ref "T1_12") (pin "G") (pinfunction "B_G") (pintype "bidirectional"))
    )
    (net (code "71") (name "Net-(T1_13-B)") (class "Default")
      (node (ref "RS11_1") (pin "2") (pinfunction "2_2") (pintype "passive"))
      (node (ref "T1_13") (pin "G") (pinfunction "B_G") (pintype "bidirectional"))
    )
    (net (code "72") (name "Net-(T1_14-B)") (class "Default")
      (node (ref "RS12_1") (pin "2") (pinfunction "2_2") (pintype "passive"))
      (node (ref "T1_14") (pin "G") (pinfunction "B_G") (pintype "bidirectional"))
    )
    (net (code "73") (name "Net-(U1-CSB{slash}IMA)") (class "Default")
      (node (ref "JP1") (pin "2") (pinfunction "2_2") (pintype "passive"))
      (node (ref "U1") (pin "41") (pinfunction "CSB/IMA_41") (pintype "input"))
    )
    (net (code "74") (name "Net-(U1-DRIVE)") (class "Default")
      (node (ref "DZT5551-13") (pin "B") (pinfunction "B_B") (pintype "bidirectional"))
      (node (ref "U1") (pin "38") (pinfunction "DRIVE_38") (pintype "output"))
    )
    (net (code "75") (name "Net-(U1-DTEN)") (class "Default")
      (node (ref "JP4") (pin "2") (pinfunction "2_2") (pintype "passive"))
      (node (ref "U1") (pin "36") (pinfunction "DTEN_36") (pintype "input"))
    )
    (net (code "76") (name "Net-(U1-IBIAS)") (class "Default")
      (node (ref "R1") (pin "2") (pinfunction "2_2") (pintype "passive"))
      (node (ref "U1") (pin "45") (pinfunction "IBIAS_45") (pintype "input"))
    )
    (net (code "77") (name "Net-(U1-ICMP)") (class "Default")
      (node (ref "R1") (pin "1") (pinfunction "1_1") (pintype "passive"))
      (node (ref "R2") (pin "2") (pinfunction "2_2") (pintype "passive"))
      (node (ref "U1") (pin "46") (pinfunction "ICMP_46") (pintype "input"))
    )
    (net (code "78") (name "Net-(U1-IMB)") (class "Default")
      (node (ref "R6") (pin "1") (pinfunction "1_1") (pintype "passive"))
      (node (ref "U$1") (pin "9") (pinfunction "9_9") (pintype "bidirectional"))
      (node (ref "U1") (pin "47") (pinfunction "IMB_47") (pintype "input"))
    )
    (net (code "79") (name "Net-(U1-IPB)") (class "Default")
      (node (ref "R6") (pin "2") (pinfunction "2_2") (pintype "passive"))
      (node (ref "U$1") (pin "7") (pinfunction "7_7") (pintype "bidirectional"))
      (node (ref "U1") (pin "48") (pinfunction "IPB_48") (pintype "input"))
    )
    (net (code "80") (name "Net-(U1-ISOMD)") (class "Default")
      (node (ref "JP3") (pin "2") (pinfunction "2_2") (pintype "passive"))
      (node (ref "U1") (pin "40") (pinfunction "ISOMD_40") (pintype "input"))
    )
    (net (code "81") (name "Net-(U1-SCK{slash}IPA)") (class "Default")
      (node (ref "JP2") (pin "2") (pinfunction "2_2") (pintype "passive"))
      (node (ref "U1") (pin "42") (pinfunction "SCK/IPA_42") (pintype "input"))
    )
    (net (code "82") (name "Net-(U1-V+)") (class "Default")
      (node (ref "C1") (pin "1") (pinfunction "1_1") (pintype "passive"))
      (node (ref "R3") (pin "1") (pinfunction "1_1") (pintype "passive"))
      (node (ref "U1") (pin "1") (pinfunction "V+_1") (pintype "power_in"))
    )
    (net (code "83") (name "Net-(U1-VREF1)") (class "Default")
      (node (ref "C4") (pin "1") (pinfunction "1_1") (pintype "passive"))
      (node (ref "U1") (pin "35") (pinfunction "VREF1_35") (pintype "power_in"))
    )
    (net (code "84") (name "Net-(U1-VREF2)") (class "Default")
      (node (ref "C5") (pin "1") (pinfunction "1_1") (pintype "passive"))
      (node (ref "U1") (pin "34") (pinfunction "VREF2_34") (pintype "power_in"))
    )
    (net (code "85") (name "Net-(U1-VREG)") (class "Default")
      (node (ref "C3") (pin "1") (pinfunction "1_1") (pintype "passive"))
      (node (ref "DZT5551-13") (pin "E") (pinfunction "E_E") (pintype "bidirectional"))
      (node (ref "JP3") (pin "1") (pinfunction "1_1") (pintype "passive"))
      (node (ref "JP4") (pin "1") (pinfunction "1_1") (pintype "passive"))
      (node (ref "R5") (pin "1") (pinfunction "1_1") (pintype "passive"))
      (node (ref "R7") (pin "1") (pinfunction "1_1") (pintype "passive"))
      (node (ref "R8") (pin "1") (pinfunction "1_1") (pintype "passive"))
      (node (ref "U1") (pin "37") (pinfunction "VREG_37") (pintype "power_in"))
    )
    (net (code "86") (name "S1_1") (class "Default")
      (node (ref "RS1_1") (pin "1") (pinfunction "1_1") (pintype "passive"))
      (node (ref "U1") (pin "25") (pinfunction "S1_25") (pintype "bidirectional"))
    )
    (net (code "87") (name "S2_1") (class "Default")
      (node (ref "RS2_1") (pin "1") (pinfunction "1_1") (pintype "passive"))
      (node (ref "U1") (pin "23") (pinfunction "S2_23") (pintype "bidirectional"))
    )
    (net (code "88") (name "S3_1") (class "Default")
      (node (ref "RS3_1") (pin "1") (pinfunction "1_1") (pintype "passive"))
      (node (ref "U1") (pin "21") (pinfunction "S3_21") (pintype "bidirectional"))
    )
    (net (code "89") (name "S4_1") (class "Default")
      (node (ref "RS4_1") (pin "1") (pinfunction "1_1") (pintype "passive"))
      (node (ref "U1") (pin "19") (pinfunction "S4_19") (pintype "bidirectional"))
    )
    (net (code "90") (name "S5_1") (class "Default")
      (node (ref "RS5_1") (pin "1") (pinfunction "1_1") (pintype "passive"))
      (node (ref "U1") (pin "17") (pinfunction "S5_17") (pintype "bidirectional"))
    )
    (net (code "91") (name "S6_1") (class "Default")
      (node (ref "RS6_1") (pin "1") (pinfunction "1_1") (pintype "passive"))
      (node (ref "U1") (pin "15") (pinfunction "S6_15") (pintype "bidirectional"))
    )
    (net (code "92") (name "S7_1") (class "Default")
      (node (ref "RS7_1") (pin "1") (pinfunction "1_1") (pintype "passive"))
      (node (ref "U1") (pin "13") (pinfunction "S7_13") (pintype "bidirectional"))
    )
    (net (code "93") (name "S8_1") (class "Default")
      (node (ref "RS8_1") (pin "1") (pinfunction "1_1") (pintype "passive"))
      (node (ref "U1") (pin "11") (pinfunction "S8_11") (pintype "bidirectional"))
    )
    (net (code "94") (name "S9_1") (class "Default")
      (node (ref "RS9_1") (pin "1") (pinfunction "1_1") (pintype "passive"))
      (node (ref "U1") (pin "9") (pinfunction "S9_9") (pintype "bidirectional"))
    )
    (net (code "95") (name "S10_1") (class "Default")
      (node (ref "RS10_1") (pin "1") (pinfunction "1_1") (pintype "passive"))
      (node (ref "U1") (pin "7") (pinfunction "S10_7") (pintype "bidirectional"))
    )
    (net (code "96") (name "S11_1") (class "Default")
      (node (ref "RS11_1") (pin "1") (pinfunction "1_1") (pintype "passive"))
      (node (ref "U1") (pin "5") (pinfunction "S11_5") (pintype "bidirectional"))
    )
    (net (code "97") (name "S12_1") (class "Default")
      (node (ref "RS12_1") (pin "1") (pinfunction "1_1") (pintype "passive"))
      (node (ref "U1") (pin "3") (pinfunction "S12_3") (pintype "bidirectional"))
    )
    (net (code "98") (name "SCK") (class "Default")
      (node (ref "JP2") (pin "3") (pinfunction "3_3") (pintype "passive"))
      (node (ref "MOLEX_SL_5") (pin "1") (pinfunction "1_1") (pintype "passive"))
      (node (ref "R5") (pin "2") (pinfunction "2_2") (pintype "passive"))
    )
    (net (code "99") (name "SDI") (class "Default")
      (node (ref "MOLEX_SL_5") (pin "4") (pinfunction "4_4") (pintype "passive"))
      (node (ref "R7") (pin "2") (pinfunction "2_2") (pintype "passive"))
      (node (ref "U1") (pin "43") (pinfunction "SDI/MC_43") (pintype "input"))
    )
    (net (code "100") (name "SDO") (class "Default")
      (node (ref "MOLEX_SL_5") (pin "3") (pinfunction "3_3") (pintype "passive"))
      (node (ref "U1") (pin "44") (pinfunction "SDO/NC_44") (pintype "output"))
    )
    (net (code "101") (name "V-_1") (class "Default")
      (node (ref "C1") (pin "2") (pinfunction "2_2") (pintype "passive"))
      (node (ref "C2") (pin "2") (pinfunction "2_2") (pintype "passive"))
      (node (ref "C3") (pin "2") (pinfunction "2_2") (pintype "passive"))
      (node (ref "C4") (pin "2") (pinfunction "2_2") (pintype "passive"))
      (node (ref "C5") (pin "2") (pinfunction "2_2") (pintype "passive"))
      (node (ref "C6") (pin "2") (pinfunction "2_2") (pintype "passive"))
      (node (ref "C7") (pin "2") (pinfunction "2_2") (pintype "passive"))
      (node (ref "C8") (pin "2") (pinfunction "2_2") (pintype "passive"))
      (node (ref "JP3") (pin "3") (pinfunction "3_3") (pintype "passive"))
      (node (ref "JP4") (pin "3") (pinfunction "3_3") (pintype "passive"))
      (node (ref "L1") (pin "2") (pinfunction "2_2") (pintype "passive"))
      (node (ref "MOLEX_SL_5") (pin "5") (pinfunction "5_5") (pintype "passive"))
      (node (ref "R2") (pin "1") (pinfunction "1_1") (pintype "passive"))
      (node (ref "U1") (pin "30") (pinfunction "V-_30") (pintype "power_in"))
      (node (ref "U1") (pin "31") (pinfunction "V-_31") (pintype "power_in"))
    )
    (net (code "102") (name "XOUT1_1") (class "Default")
      (node (ref "MOLEX_SL_2") (pin "2") (pinfunction "2_2") (pintype "passive"))
      (node (ref "U$1") (pin "1") (pinfunction "1_1") (pintype "bidirectional"))
    )
    (net (code "103") (name "XOUT3_1") (class "Default")
      (node (ref "MOLEX_SL_2") (pin "1") (pinfunction "1_1") (pintype "passive"))
      (node (ref "U$1") (pin "3") (pinfunction "3_3") (pintype "bidirectional"))
    )
    (net (code "104") (name "unconnected-(C1_1-Pad2)") (class "Default")
      (node (ref "C1_1") (pin "2") (pinfunction "2_2") (pintype "passive"))
    )
    (net (code "105") (name "unconnected-(U$1-Pad2)") (class "Default")
      (node (ref "U$1") (pin "2") (pinfunction "2_2") (pintype "bidirectional"))
    )
    (net (code "106") (name "unconnected-(U$1-Pad5)") (class "Default")
      (node (ref "U$1") (pin "5") (pinfunction "5_5") (pintype "bidirectional"))
    )
    (net (code "107") (name "unconnected-(U1-GPIO1-Pad27)") (class "Default")
      (node (ref "U1") (pin "27") (pinfunction "GPIO1_27") (pintype "bidirectional"))
    )
    (net (code "108") (name "unconnected-(U1-GPIO2-Pad28)") (class "Default")
      (node (ref "U1") (pin "28") (pinfunction "GPIO2_28") (pintype "bidirectional"))
    )
    (net (code "109") (name "unconnected-(U1-GPIO3-Pad29)") (class "Default")
      (node (ref "U1") (pin "29") (pinfunction "GPIO3_29") (pintype "bidirectional"))
    )
    (net (code "110") (name "unconnected-(U1-GPIO4-Pad32)") (class "Default")
      (node (ref "U1") (pin "32") (pinfunction "GPIO4_32") (pintype "bidirectional"))
    )
    (net (code "111") (name "unconnected-(U1-GPIO5-Pad33)") (class "Default")
      (node (ref "U1") (pin "33") (pinfunction "GPIO5_33") (pintype "bidirectional"))
    )
    (net (code "112") (name "unconnected-(U1-WDT-Pad39)") (class "Default")
      (node (ref "U1") (pin "39") (pinfunction "WDT_39") (pintype "output"))
    )
  )
)
